# DieuKhien_schematic.net
KiCad netlist of a schematic drawn in Altium Designer
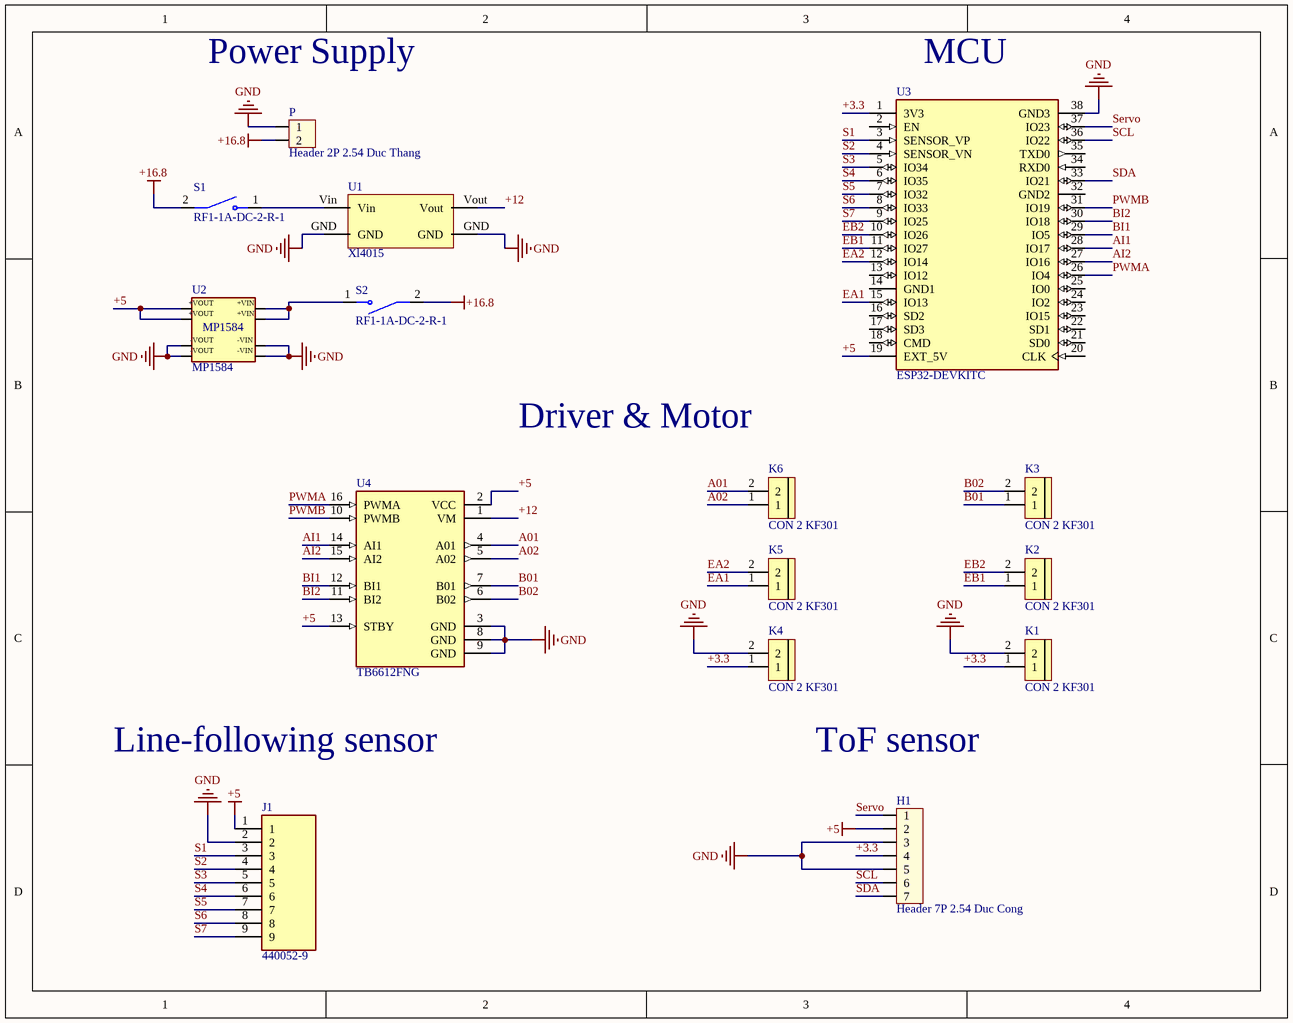
[diagram p0: DieuKhien_schematic.SchDoc]

(export (version "E")
  (design (tool "Eeschema 10.0.6"))
  (components
    (comp (ref "H1")
      (value "Header 7P 2.54 Duc Cong")
      (footprint "Header 7P DC 2.54")
      (description "Cắm")
      (libsource (lib "Header") (part "Header 7P 2.54 Duc Cong"))
    )
    (comp (ref "J1")
      (value "440052-9")
      (footprint "TE_440052-9")
      (libsource (lib "440052-9") (part "440052-9"))
    )
    (comp (ref "K1")
      (value "CON 2 KF301")
      (footprint "Con 2 KF301 5.08")
      (description "Cắm")
      (libsource (lib "Connector") (part "CON 2 KF301"))
    )
    (comp (ref "K2")
      (value "CON 2 KF301")
      (footprint "Con 2 KF301 5.08")
      (description "Cắm")
      (libsource (lib "Connector") (part "CON 2 KF301"))
    )
    (comp (ref "K3")
      (value "CON 2 KF301")
      (footprint "Con 2 KF301 5.08")
      (description "Cắm")
      (libsource (lib "Connector") (part "CON 2 KF301"))
    )
    (comp (ref "K4")
      (value "CON 2 KF301")
      (footprint "Con 2 KF301 5.08")
      (description "Cắm")
      (libsource (lib "Connector") (part "CON 2 KF301"))
    )
    (comp (ref "K5")
      (value "CON 2 KF301")
      (footprint "Con 2 KF301 5.08")
      (description "Cắm")
      (libsource (lib "Connector") (part "CON 2 KF301"))
    )
    (comp (ref "K6")
      (value "CON 2 KF301")
      (footprint "Con 2 KF301 5.08")
      (description "Cắm")
      (libsource (lib "Connector") (part "CON 2 KF301"))
    )
    (comp (ref "P")
      (value "Header 2P 2.54 Duc Thang")
      (footprint "XH2.54M-2")
      (description "Cắm")
      (libsource (lib "Header") (part "Header 2P 2.54 Duc Thang"))
    )
    (comp (ref "S1")
      (value "RF1-1A-DC-2-R-1")
      (footprint "SW_RF1-1A-DC-2-R-1")
      (description "Switch, Mini Rocker, 2P SPST OFF-ON, Red w/ Print, VDC ¦ Switch Components RF1-1A-DC-2-R-1")
      (fields (field (name "MF") "Switch Components"))
      (libsource (lib "RF1-1A-DC-2-R-1") (part "RF1-1A-DC-2-R-1"))
    )
    (comp (ref "S2")
      (value "RF1-1A-DC-2-R-1")
      (footprint "SW_RF1-1A-DC-2-R-1")
      (description "Switch, Mini Rocker, 2P SPST OFF-ON, Red w/ Print, VDC ¦ Switch Components RF1-1A-DC-2-R-1")
      (fields (field (name "MF") "Switch Components"))
      (libsource (lib "RF1-1A-DC-2-R-1") (part "RF1-1A-DC-2-R-1"))
    )
    (comp (ref "U1") (value "Xl4015") (footprint "XL4015") (libsource (lib "XL4015") (part "Xl4015")))
    (comp (ref "U2") (value "MP1584") (footprint "MP1584") (libsource (lib "MP1584") (part "MP1584")))
    (comp (ref "U3")
      (value "ESP32-DEVKITC")
      (footprint "MODULE_ESP32-DEVKITC")
      (fields (field (name "MF") "Espressif Systems"))
      (libsource (lib "ESP32-DEVKITC") (part "ESP32-DEVKITC"))
    )
    (comp (ref "U4")
      (value "TB6612FNG")
      (footprint "MODULE_ROB-14450")
      (description "TB6612FNG Motor Controller/Driver Power Management Evaluation Board")
      (fields (field (name "MP") "ROB-14450") (field (name "MF") "SparkFun Electronics"))
      (libsource (lib "ROB-14450") (part "ROB-14450"))
    )
  )
  (nets
    (net (code "1") (name "+5") (class "Default")
      (node (ref "H1") (pin "2") (pinfunction "2_2") (pintype "passive"))
      (node (ref "J1") (pin "1") (pinfunction "1_1") (pintype "passive"))
      (node (ref "U2") (pin "+VOUT") (pintype "power_in"))
      (node (ref "U3") (pin "19") (pinfunction "EXT_5V_19") (pintype "power_in"))
      (node (ref "U4") (pin "13") (pinfunction "STBY_13") (pintype "input"))
      (node (ref "U4") (pin "2") (pinfunction "VCC_2") (pintype "power_in"))
    )
    (net (code "2") (name "+16.8") (class "Default")
      (node (ref "P") (pin "2") (pinfunction "2_2") (pintype "passive"))
      (node (ref "S1") (pin "2") (pinfunction "2_2") (pintype "passive"))
      (node (ref "S2") (pin "2") (pinfunction "2_2") (pintype "passive"))
    )
    (net (code "3") (name "/+3.3") (class "Default")
      (node (ref "H1") (pin "4") (pinfunction "4_4") (pintype "passive"))
      (node (ref "K1") (pin "1") (pinfunction "1_1") (pintype "passive"))
      (node (ref "K4") (pin "1") (pinfunction "1_1") (pintype "passive"))
      (node (ref "U3") (pin "1") (pinfunction "3V3_1") (pintype "power_in"))
    )
    (net (code "4") (name "/+12") (class "Default")
      (node (ref "U1") (pin "Vout") (pinfunction "Vout_Vout") (pintype "passive"))
      (node (ref "U4") (pin "1") (pinfunction "VM_1") (pintype "power_in"))
    )
    (net (code "5") (name "/A01") (class "Default")
      (node (ref "K6") (pin "2") (pinfunction "2_2") (pintype "passive"))
      (node (ref "U4") (pin "4") (pinfunction "A01_4") (pintype "output"))
    )
    (net (code "6") (name "/A02") (class "Default")
      (node (ref "K6") (pin "1") (pinfunction "1_1") (pintype "passive"))
      (node (ref "U4") (pin "5") (pinfunction "A02_5") (pintype "output"))
    )
    (net (code "7") (name "/AI1") (class "Default")
      (node (ref "U3") (pin "28") (pinfunction "IO17_28") (pintype "bidirectional"))
      (node (ref "U4") (pin "14") (pinfunction "AI1_14") (pintype "input"))
    )
    (net (code "8") (name "/AI2") (class "Default")
      (node (ref "U3") (pin "27") (pinfunction "IO16_27") (pintype "bidirectional"))
      (node (ref "U4") (pin "15") (pinfunction "AI2_15") (pintype "input"))
    )
    (net (code "9") (name "/B01") (class "Default")
      (node (ref "K3") (pin "1") (pinfunction "1_1") (pintype "passive"))
      (node (ref "U4") (pin "7") (pinfunction "B01_7") (pintype "output"))
    )
    (net (code "10") (name "/B02") (class "Default")
      (node (ref "K3") (pin "2") (pinfunction "2_2") (pintype "passive"))
      (node (ref "U4") (pin "6") (pinfunction "B02_6") (pintype "output"))
    )
    (net (code "11") (name "/BI1") (class "Default")
      (node (ref "U3") (pin "29") (pinfunction "IO5_29") (pintype "bidirectional"))
      (node (ref "U4") (pin "12") (pinfunction "BI1_12") (pintype "input"))
    )
    (net (code "12") (name "/BI2") (class "Default")
      (node (ref "U3") (pin "30") (pinfunction "IO18_30") (pintype "bidirectional"))
      (node (ref "U4") (pin "11") (pinfunction "BI2_11") (pintype "input"))
    )
    (net (code "13") (name "/EA1") (class "Default")
      (node (ref "K5") (pin "1") (pinfunction "1_1") (pintype "passive"))
      (node (ref "U3") (pin "15") (pinfunction "IO13_15") (pintype "bidirectional"))
    )
    (net (code "14") (name "/EA2") (class "Default")
      (node (ref "K5") (pin "2") (pinfunction "2_2") (pintype "passive"))
      (node (ref "U3") (pin "12") (pinfunction "IO14_12") (pintype "bidirectional"))
    )
    (net (code "15") (name "/EB1") (class "Default")
      (node (ref "K2") (pin "1") (pinfunction "1_1") (pintype "passive"))
      (node (ref "U3") (pin "11") (pinfunction "IO27_11") (pintype "bidirectional"))
    )
    (net (code "16") (name "/EB2") (class "Default")
      (node (ref "K2") (pin "2") (pinfunction "2_2") (pintype "passive"))
      (node (ref "U3") (pin "10") (pinfunction "IO26_10") (pintype "bidirectional"))
    )
    (net (code "17") (name "/PWMA") (class "Default")
      (node (ref "U3") (pin "26") (pinfunction "IO4_26") (pintype "bidirectional"))
      (node (ref "U4") (pin "16") (pinfunction "PWMA_16") (pintype "input"))
    )
    (net (code "18") (name "/PWMB") (class "Default")
      (node (ref "U3") (pin "31") (pinfunction "IO19_31") (pintype "bidirectional"))
      (node (ref "U4") (pin "10") (pinfunction "PWMB_10") (pintype "input"))
    )
    (net (code "19") (name "/S1") (class "Default")
      (node (ref "J1") (pin "3") (pinfunction "3_3") (pintype "passive"))
      (node (ref "U3") (pin "3") (pinfunction "SENSOR_VP_3") (pintype "input"))
    )
    (net (code "20") (name "/S2") (class "Default")
      (node (ref "J1") (pin "4") (pinfunction "4_4") (pintype "passive"))
      (node (ref "U3") (pin "4") (pinfunction "SENSOR_VN_4") (pintype "input"))
    )
    (net (code "21") (name "/S3") (class "Default")
      (node (ref "J1") (pin "5") (pinfunction "5_5") (pintype "passive"))
      (node (ref "U3") (pin "5") (pinfunction "IO34_5") (pintype "bidirectional"))
    )
    (net (code "22") (name "/S4") (class "Default")
      (node (ref "J1") (pin "6") (pinfunction "6_6") (pintype "passive"))
      (node (ref "U3") (pin "6") (pinfunction "IO35_6") (pintype "bidirectional"))
    )
    (net (code "23") (name "/S5") (class "Default")
      (node (ref "J1") (pin "7") (pinfunction "7_7") (pintype "passive"))
      (node (ref "U3") (pin "7") (pinfunction "IO32_7") (pintype "bidirectional"))
    )
    (net (code "24") (name "/S6") (class "Default")
      (node (ref "J1") (pin "8") (pinfunction "8_8") (pintype "passive"))
      (node (ref "U3") (pin "8") (pinfunction "IO33_8") (pintype "bidirectional"))
    )
    (net (code "25") (name "/S7") (class "Default")
      (node (ref "J1") (pin "9") (pinfunction "9_9") (pintype "passive"))
      (node (ref "U3") (pin "9") (pinfunction "IO25_9") (pintype "bidirectional"))
    )
    (net (code "26") (name "/SCL") (class "Default")
      (node (ref "H1") (pin "6") (pinfunction "6_6") (pintype "passive"))
      (node (ref "U3") (pin "36") (pinfunction "IO22_36") (pintype "bidirectional"))
    )
    (net (code "27") (name "/SDA") (class "Default")
      (node (ref "H1") (pin "7") (pinfunction "7_7") (pintype "passive"))
      (node (ref "U3") (pin "33") (pinfunction "IO21_33") (pintype "bidirectional"))
    )
    (net (code "28") (name "/Servo") (class "Default")
      (node (ref "H1") (pin "1") (pinfunction "1_1") (pintype "passive"))
      (node (ref "U3") (pin "37") (pinfunction "IO23_37") (pintype "bidirectional"))
    )
    (net (code "29") (name "GND") (class "Default")
      (node (ref "H1") (pin "3") (pinfunction "3_3") (pintype "passive"))
      (node (ref "H1") (pin "5") (pinfunction "5_5") (pintype "passive"))
      (node (ref "J1") (pin "2") (pinfunction "2_2") (pintype "passive"))
      (node (ref "K1") (pin "2") (pinfunction "2_2") (pintype "passive"))
      (node (ref "K4") (pin "2") (pinfunction "2_2") (pintype "passive"))
      (node (ref "P") (pin "1") (pinfunction "1_1") (pintype "passive"))
      (node (ref "U1") (pin "GND") (pinfunction "GND_GND") (pintype "passive"))
      (node (ref "U2") (pin "-VIN") (pintype "power_in"))
      (node (ref "U2") (pin "-VOUT") (pintype "power_in"))
      (node (ref "U3") (pin "38") (pinfunction "GND3_38") (pintype "power_in"))
      (node (ref "U4") (pin "3") (pinfunction "GND_3") (pintype "power_in"))
      (node (ref "U4") (pin "8") (pinfunction "GND_8") (pintype "power_in"))
      (node (ref "U4") (pin "9") (pinfunction "GND_9") (pintype "power_in"))
    )
    (net (code "30") (name "Net-(S1-Pad1)") (class "Default")
      (node (ref "S1") (pin "1") (pinfunction "1_1") (pintype "passive"))
      (node (ref "U1") (pin "Vin") (pinfunction "Vin_Vin") (pintype "passive"))
    )
    (net (code "31") (name "Net-(S2-Pad1)") (class "Default")
      (node (ref "S2") (pin "1") (pinfunction "1_1") (pintype "passive"))
      (node (ref "U2") (pin "+VIN") (pintype "power_in"))
    )
    (net (code "32") (name "unconnected-(U3-CLK-Pad20)") (class "Default")
      (node (ref "U3") (pin "20") (pinfunction "CLK_20") (pintype "input"))
    )
    (net (code "33") (name "unconnected-(U3-CMD-Pad18)") (class "Default")
      (node (ref "U3") (pin "18") (pinfunction "CMD_18") (pintype "bidirectional"))
    )
    (net (code "34") (name "unconnected-(U3-EN-Pad2)") (class "Default")
      (node (ref "U3") (pin "2") (pinfunction "EN_2") (pintype "input"))
    )
    (net (code "35") (name "unconnected-(U3-GND1-Pad14)") (class "Default")
      (node (ref "U3") (pin "14") (pinfunction "GND1_14") (pintype "power_in"))
    )
    (net (code "36") (name "unconnected-(U3-GND2-Pad32)") (class "Default")
      (node (ref "U3") (pin "32") (pinfunction "GND2_32") (pintype "power_in"))
    )
    (net (code "37") (name "unconnected-(U3-IO0-Pad25)") (class "Default")
      (node (ref "U3") (pin "25") (pinfunction "IO0_25") (pintype "bidirectional"))
    )
    (net (code "38") (name "unconnected-(U3-IO2-Pad24)") (class "Default")
      (node (ref "U3") (pin "24") (pinfunction "IO2_24") (pintype "bidirectional"))
    )
    (net (code "39") (name "unconnected-(U3-IO12-Pad13)") (class "Default")
      (node (ref "U3") (pin "13") (pinfunction "IO12_13") (pintype "bidirectional"))
    )
    (net (code "40") (name "unconnected-(U3-IO15-Pad23)") (class "Default")
      (node (ref "U3") (pin "23") (pinfunction "IO15_23") (pintype "bidirectional"))
    )
    (net (code "41") (name "unconnected-(U3-RXD0-Pad34)") (class "Default")
      (node (ref "U3") (pin "34") (pinfunction "RXD0_34") (pintype "input"))
    )
    (net (code "42") (name "unconnected-(U3-SD0-Pad21)") (class "Default")
      (node (ref "U3") (pin "21") (pinfunction "SD0_21") (pintype "bidirectional"))
    )
    (net (code "43") (name "unconnected-(U3-SD1-Pad22)") (class "Default")
      (node (ref "U3") (pin "22") (pinfunction "SD1_22") (pintype "bidirectional"))
    )
    (net (code "44") (name "unconnected-(U3-SD2-Pad16)") (class "Default")
      (node (ref "U3") (pin "16") (pinfunction "SD2_16") (pintype "bidirectional"))
    )
    (net (code "45") (name "unconnected-(U3-SD3-Pad17)") (class "Default")
      (node (ref "U3") (pin "17") (pinfunction "SD3_17") (pintype "bidirectional"))
    )
    (net (code "46") (name "unconnected-(U3-TXD0-Pad35)") (class "Default")
      (node (ref "U3") (pin "35") (pinfunction "TXD0_35") (pintype "output"))
    )
  )
)
